# fab_scope.net
KiCad netlist of a schematic drawn in EAGLE
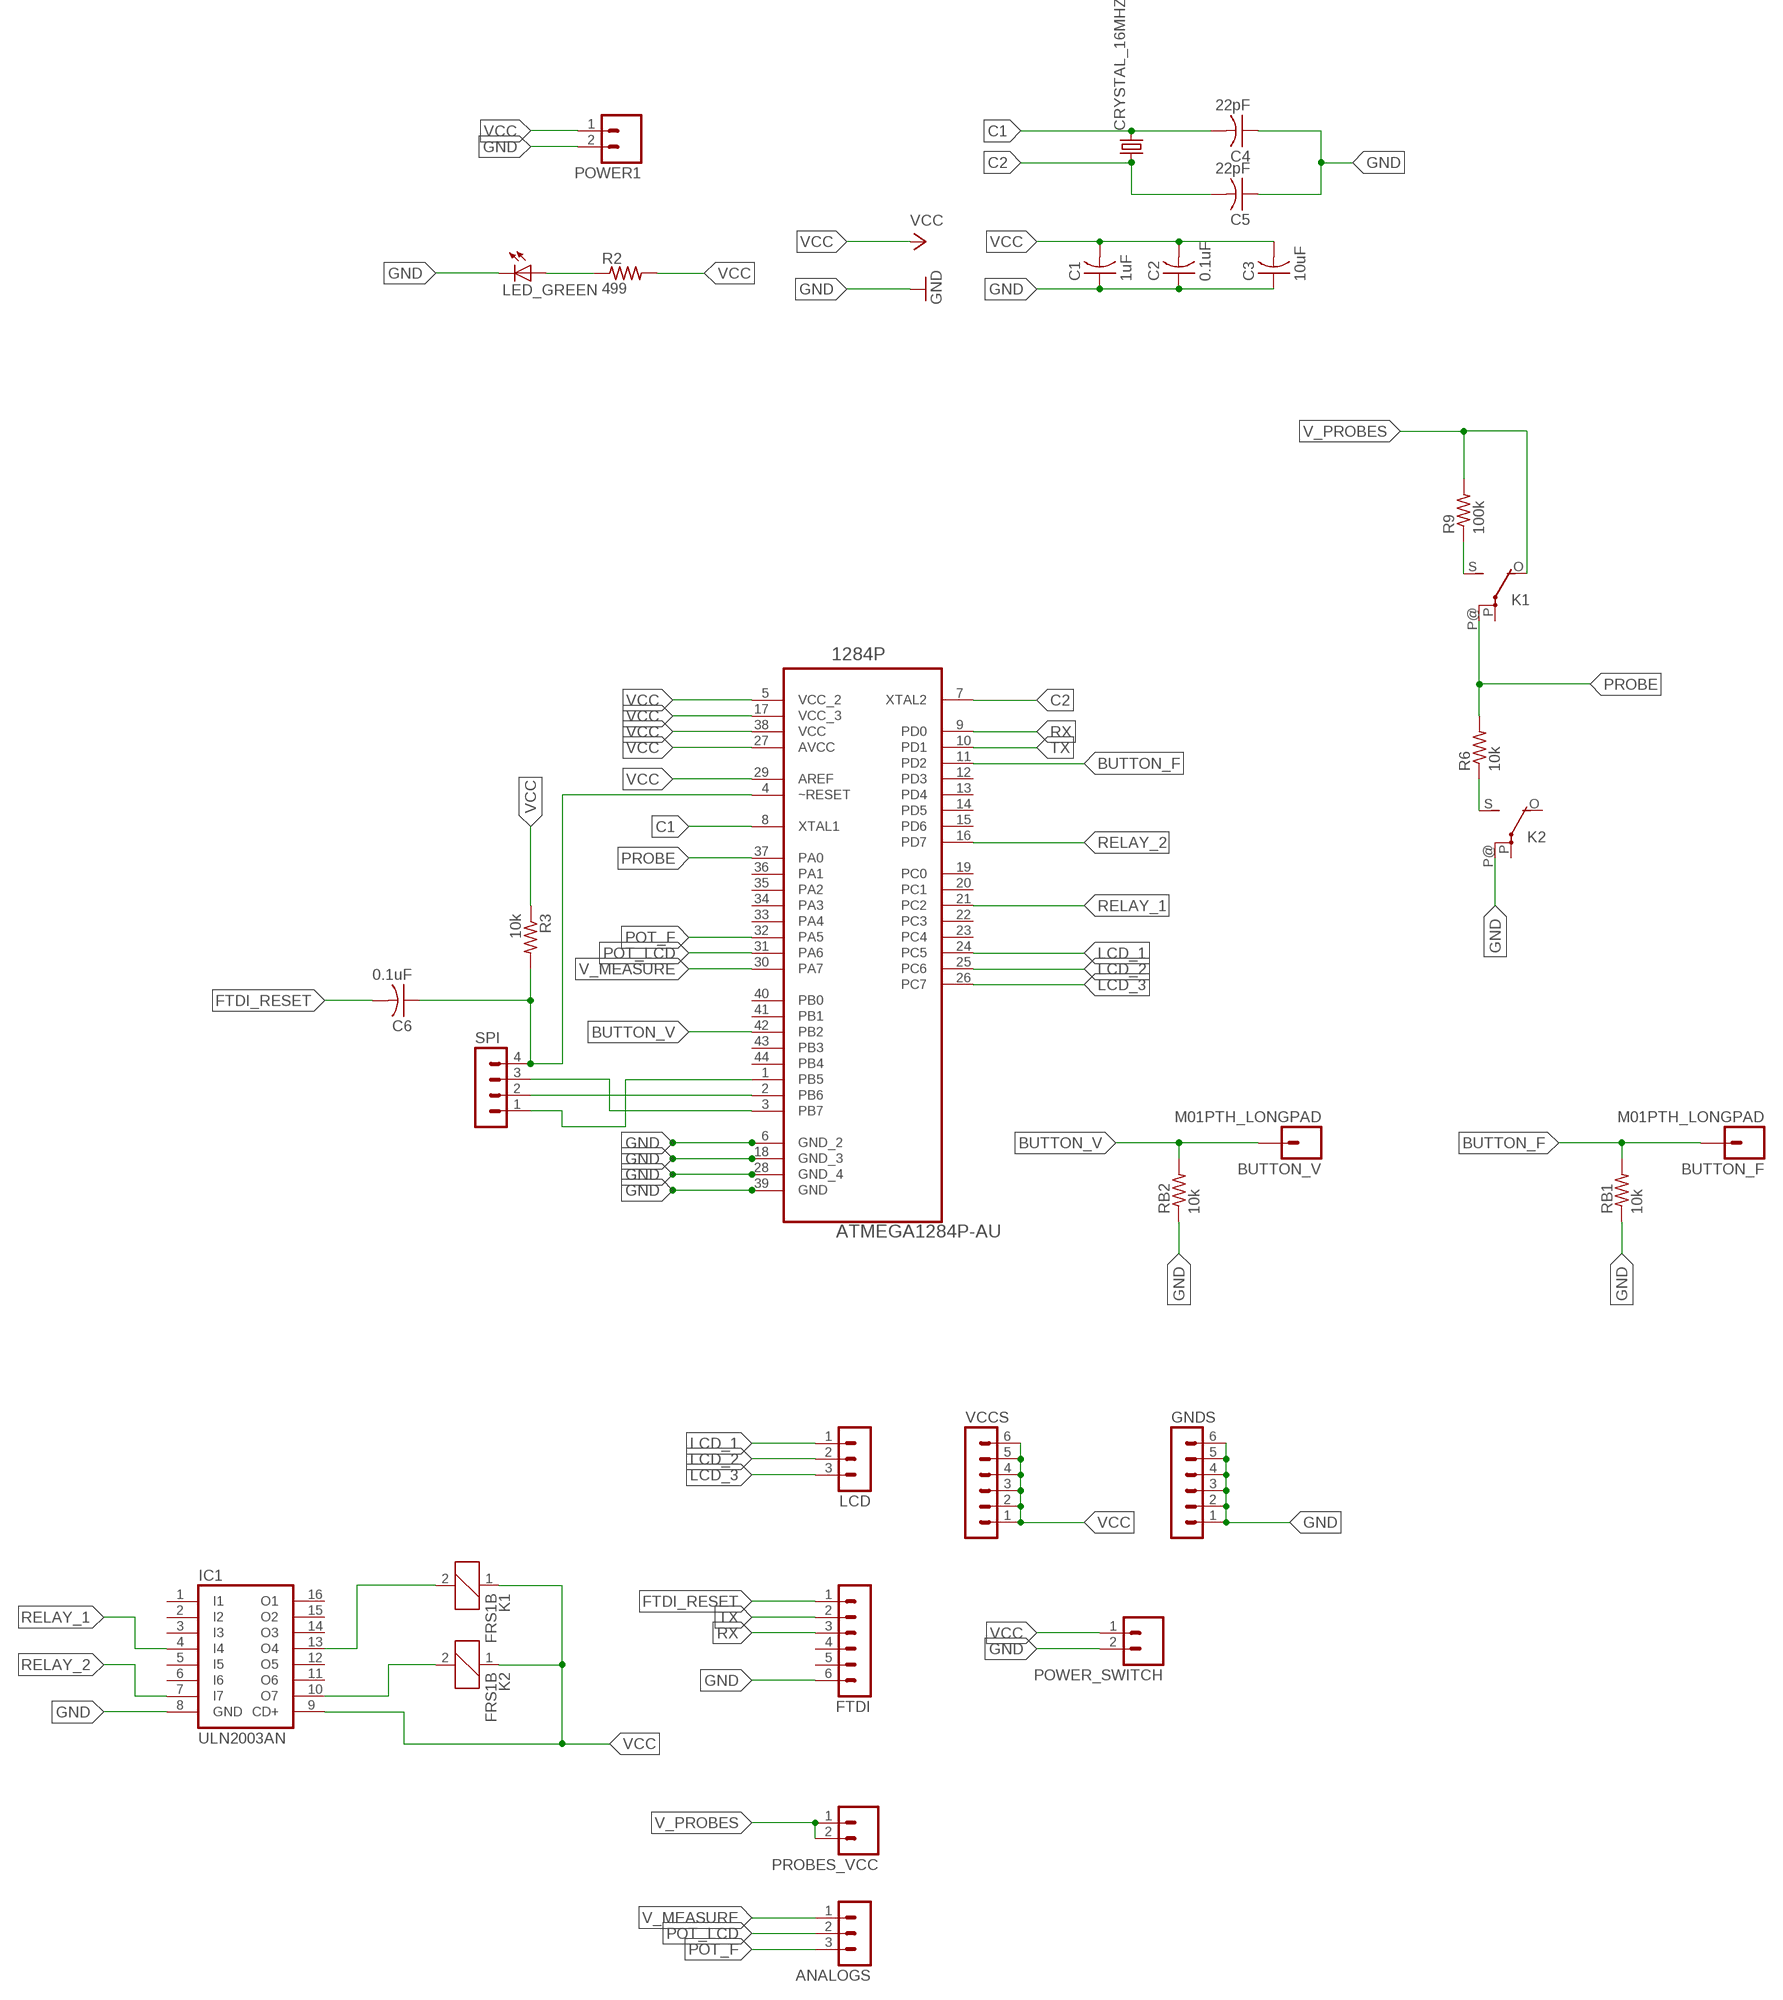
[diagram p0: schematic, sheet 1]

(export (version "E")
  (design (tool "Eeschema 10.0.6"))
  (components
    (comp (ref "1284P")
      (value "ATMEGA1284P-AU")
      (footprint "eagle-import:QFP80P1200X1200X120-44N")
      (libsource (lib "eagle-import") (part "ATMEGA1284P-AU"))
    )
    (comp (ref "ANALOGS")
      (value "MA03-1")
      (footprint "eagle-import:MA03-1")
      (libsource (lib "eagle-import") (part "MA03-1"))
    )
    (comp (ref "BUTTON_F")
      (value "M01PTH_LONGPAD")
      (footprint "eagle-import:1X01_LONGPAD")
      (libsource (lib "eagle-import") (part "M01PTH_LONGPAD"))
    )
    (comp (ref "BUTTON_V")
      (value "M01PTH_LONGPAD")
      (footprint "eagle-import:1X01_LONGPAD")
      (libsource (lib "eagle-import") (part "M01PTH_LONGPAD"))
    )
    (comp (ref "C1")
      (value "1uF")
      (footprint "eagle-import:C1206")
      (libsource (lib "eagle-import") (part "CAP-US1206"))
    )
    (comp (ref "C2")
      (value "0.1uF")
      (footprint "eagle-import:C1206")
      (libsource (lib "eagle-import") (part "CAP-US1206"))
    )
    (comp (ref "C3")
      (value "10uF")
      (footprint "eagle-import:C1206")
      (libsource (lib "eagle-import") (part "CAP-US1206"))
    )
    (comp (ref "C4")
      (value "22pF")
      (footprint "eagle-import:C1206")
      (libsource (lib "eagle-import") (part "CAP-US1206"))
    )
    (comp (ref "C5")
      (value "22pF")
      (footprint "eagle-import:C1206")
      (libsource (lib "eagle-import") (part "CAP-US1206"))
    )
    (comp (ref "C6")
      (value "0.1uF")
      (footprint "eagle-import:C1206")
      (libsource (lib "eagle-import") (part "CAP-US1206"))
    )
    (comp (ref "CRYSTAL_16MHZ")
      (value "CRYSTALHC49UP")
      (footprint "eagle-import:HC49UP")
      (libsource (lib "eagle-import") (part "CRYSTALHC49UP"))
    )
    (comp (ref "FTDI")
      (value "MA06-1")
      (footprint "eagle-import:MA06-1")
      (libsource (lib "eagle-import") (part "MA06-1"))
    )
    (comp (ref "GNDS")
      (value "MA06-1")
      (footprint "eagle-import:MA06-1")
      (libsource (lib "eagle-import") (part "MA06-1"))
    )
    (comp (ref "IC1")
      (value "ULN2003AN")
      (footprint "eagle-import:DIL16")
      (libsource (lib "eagle-import") (part "ULN2003AN"))
    )
    (comp (ref "K1")
      (value "FRS1B")
      (footprint "eagle-import:FRS1B")
      (libsource (lib "eagle-import") (part "FRS1B"))
    )
    (comp (ref "K2")
      (value "FRS1B")
      (footprint "eagle-import:FRS1B")
      (libsource (lib "eagle-import") (part "FRS1B"))
    )
    (comp (ref "LCD")
      (value "MA03-1")
      (footprint "eagle-import:MA03-1")
      (libsource (lib "eagle-import") (part "MA03-1"))
    )
    (comp (ref "LED_GREEN")
      (value "LED1206")
      (footprint "eagle-import:1206")
      (libsource (lib "eagle-import") (part "LED1206"))
    )
    (comp (ref "POWER1")
      (value "M02")
      (footprint "eagle-import:02P")
      (libsource (lib "eagle-import") (part "M02"))
    )
    (comp (ref "POWER_SWITCH")
      (value "M02")
      (footprint "eagle-import:02P")
      (libsource (lib "eagle-import") (part "M02"))
    )
    (comp (ref "PROBES_VCC")
      (value "M02")
      (footprint "eagle-import:02P")
      (libsource (lib "eagle-import") (part "M02"))
    )
    (comp (ref "R2")
      (value "499")
      (footprint "eagle-import:R1206")
      (libsource (lib "eagle-import") (part "RES-US1206"))
    )
    (comp (ref "R3")
      (value "10k")
      (footprint "eagle-import:R1206")
      (libsource (lib "eagle-import") (part "RES-US1206"))
    )
    (comp (ref "R6")
      (value "10k")
      (footprint "eagle-import:R1206")
      (libsource (lib "eagle-import") (part "RES-US1206"))
    )
    (comp (ref "R9")
      (value "100k")
      (footprint "eagle-import:R1206")
      (libsource (lib "eagle-import") (part "RES-US1206"))
    )
    (comp (ref "RB1")
      (value "10k")
      (footprint "eagle-import:R1206")
      (libsource (lib "eagle-import") (part "RES-US1206"))
    )
    (comp (ref "RB2")
      (value "10k")
      (footprint "eagle-import:R1206")
      (libsource (lib "eagle-import") (part "RES-US1206"))
    )
    (comp (ref "SPI")
      (value "MA04-1")
      (footprint "eagle-import:MA04-1")
      (libsource (lib "eagle-import") (part "MA04-1"))
    )
    (comp (ref "VCCS")
      (value "MA06-1")
      (footprint "eagle-import:MA06-1")
      (libsource (lib "eagle-import") (part "MA06-1"))
    )
  )
  (nets
    (net (code "1") (name "BUTTON_F") (class "Default")
      (node (ref "1284P") (pin "11") (pinfunction "PD2_11") (pintype "bidirectional"))
      (node (ref "BUTTON_F") (pin "1") (pinfunction "1_1") (pintype "passive"))
      (node (ref "RB1") (pin "2") (pinfunction "2_2") (pintype "passive"))
    )
    (net (code "2") (name "BUTTON_V") (class "Default")
      (node (ref "1284P") (pin "42") (pinfunction "PB2_42") (pintype "bidirectional"))
      (node (ref "BUTTON_V") (pin "1") (pinfunction "1_1") (pintype "passive"))
      (node (ref "RB2") (pin "2") (pinfunction "2_2") (pintype "passive"))
    )
    (net (code "3") (name "C1") (class "Default")
      (node (ref "1284P") (pin "8") (pinfunction "XTAL1_8") (pintype "input"))
      (node (ref "C4") (pin "2") (pinfunction "2_2") (pintype "passive"))
      (node (ref "CRYSTAL_16MHZ") (pin "2") (pinfunction "2_2") (pintype "passive"))
    )
    (net (code "4") (name "C2") (class "Default")
      (node (ref "1284P") (pin "7") (pinfunction "XTAL2_7") (pintype "output"))
      (node (ref "C5") (pin "2") (pinfunction "2_2") (pintype "passive"))
      (node (ref "CRYSTAL_16MHZ") (pin "1") (pinfunction "1_1") (pintype "passive"))
    )
    (net (code "5") (name "FTDI_RESET") (class "Default")
      (node (ref "C6") (pin "2") (pinfunction "2_2") (pintype "passive"))
      (node (ref "FTDI") (pin "1") (pinfunction "1_1") (pintype "passive"))
    )
    (net (code "6") (name "GND") (class "Default")
      (node (ref "1284P") (pin "6") (pinfunction "GND_2_6") (pintype "passive"))
      (node (ref "C1") (pin "1") (pinfunction "1_1") (pintype "passive"))
      (node (ref "C2") (pin "1") (pinfunction "1_1") (pintype "passive"))
      (node (ref "C3") (pin "1") (pinfunction "1_1") (pintype "passive"))
      (node (ref "C4") (pin "1") (pinfunction "1_1") (pintype "passive"))
      (node (ref "C5") (pin "1") (pinfunction "1_1") (pintype "passive"))
      (node (ref "FTDI") (pin "6") (pinfunction "6_6") (pintype "passive"))
      (node (ref "GNDS") (pin "1") (pinfunction "1_1") (pintype "passive"))
      (node (ref "GNDS") (pin "2") (pinfunction "2_2") (pintype "passive"))
      (node (ref "GNDS") (pin "3") (pinfunction "3_3") (pintype "passive"))
      (node (ref "GNDS") (pin "4") (pinfunction "4_4") (pintype "passive"))
      (node (ref "GNDS") (pin "5") (pinfunction "5_5") (pintype "passive"))
      (node (ref "GNDS") (pin "6") (pinfunction "6_6") (pintype "passive"))
      (node (ref "IC1") (pin "8") (pinfunction "GND_8") (pintype "power_in"))
      (node (ref "K2") (pin "P@") (pinfunction "P_P@") (pintype "passive"))
      (node (ref "LED_GREEN") (pin "2") (pinfunction "C_2") (pintype "passive"))
      (node (ref "POWER1") (pin "2") (pinfunction "2_2") (pintype "passive"))
      (node (ref "POWER_SWITCH") (pin "2") (pinfunction "2_2") (pintype "passive"))
      (node (ref "RB1") (pin "1") (pinfunction "1_1") (pintype "passive"))
      (node (ref "RB2") (pin "1") (pinfunction "1_1") (pintype "passive"))
    )
    (net (code "7") (name "LCD_1") (class "Default")
      (node (ref "1284P") (pin "24") (pinfunction "PC5_24") (pintype "bidirectional"))
      (node (ref "LCD") (pin "1") (pinfunction "1_1") (pintype "passive"))
    )
    (net (code "8") (name "LCD_2") (class "Default")
      (node (ref "1284P") (pin "25") (pinfunction "PC6_25") (pintype "bidirectional"))
      (node (ref "LCD") (pin "2") (pinfunction "2_2") (pintype "passive"))
    )
    (net (code "9") (name "LCD_3") (class "Default")
      (node (ref "1284P") (pin "26") (pinfunction "PC7_26") (pintype "bidirectional"))
      (node (ref "LCD") (pin "3") (pinfunction "3_3") (pintype "passive"))
    )
    (net (code "10") (name "Net-(1284P-PB5)") (class "Default")
      (node (ref "1284P") (pin "1") (pinfunction "PB5_1") (pintype "bidirectional"))
      (node (ref "SPI") (pin "1") (pinfunction "1_1") (pintype "passive"))
    )
    (net (code "11") (name "Net-(1284P-PB6)") (class "Default")
      (node (ref "1284P") (pin "2") (pinfunction "PB6_2") (pintype "bidirectional"))
      (node (ref "SPI") (pin "2") (pinfunction "2_2") (pintype "passive"))
    )
    (net (code "12") (name "Net-(1284P-PB7)") (class "Default")
      (node (ref "1284P") (pin "3") (pinfunction "PB7_3") (pintype "bidirectional"))
      (node (ref "SPI") (pin "3") (pinfunction "3_3") (pintype "passive"))
    )
    (net (code "13") (name "Net-(1284P-~{RESET})") (class "Default")
      (node (ref "1284P") (pin "4") (pinfunction "~{RESET}_4") (pintype "input"))
      (node (ref "C6") (pin "1") (pinfunction "1_1") (pintype "passive"))
      (node (ref "R3") (pin "2") (pinfunction "2_2") (pintype "passive"))
      (node (ref "SPI") (pin "4") (pinfunction "4_4") (pintype "passive"))
    )
    (net (code "14") (name "Net-(IC1-O4)") (class "Default")
      (node (ref "IC1") (pin "13") (pinfunction "O4_13") (pintype "open_collector"))
      (node (ref "K1") (pin "2") (pinfunction "2_2") (pintype "passive"))
    )
    (net (code "15") (name "Net-(IC1-O7)") (class "Default")
      (node (ref "IC1") (pin "10") (pinfunction "O7_10") (pintype "open_collector"))
      (node (ref "K2") (pin "2") (pinfunction "2_2") (pintype "passive"))
    )
    (net (code "16") (name "Net-(K1-PadS)") (class "Default")
      (node (ref "K1") (pin "S") (pinfunction "S_S") (pintype "passive"))
      (node (ref "R9") (pin "1") (pinfunction "1_1") (pintype "passive"))
    )
    (net (code "17") (name "Net-(K2-PadS)") (class "Default")
      (node (ref "K2") (pin "S") (pinfunction "S_S") (pintype "passive"))
      (node (ref "R6") (pin "1") (pinfunction "1_1") (pintype "passive"))
    )
    (net (code "18") (name "Net-(LED_GREEN-A)") (class "Default")
      (node (ref "LED_GREEN") (pin "1") (pinfunction "A_1") (pintype "passive"))
      (node (ref "R2") (pin "1") (pinfunction "1_1") (pintype "passive"))
    )
    (net (code "19") (name "POT_F") (class "Default")
      (node (ref "1284P") (pin "32") (pinfunction "PA5_32") (pintype "bidirectional"))
      (node (ref "ANALOGS") (pin "3") (pinfunction "3_3") (pintype "passive"))
    )
    (net (code "20") (name "POT_LCD") (class "Default")
      (node (ref "1284P") (pin "31") (pinfunction "PA6_31") (pintype "bidirectional"))
      (node (ref "ANALOGS") (pin "2") (pinfunction "2_2") (pintype "passive"))
    )
    (net (code "21") (name "PROBE") (class "Default")
      (node (ref "1284P") (pin "37") (pinfunction "PA0_37") (pintype "bidirectional"))
      (node (ref "K1") (pin "P@") (pinfunction "P_P@") (pintype "passive"))
      (node (ref "R6") (pin "2") (pinfunction "2_2") (pintype "passive"))
    )
    (net (code "22") (name "RELAY_1") (class "Default")
      (node (ref "1284P") (pin "21") (pinfunction "PC2_21") (pintype "bidirectional"))
      (node (ref "IC1") (pin "4") (pinfunction "I4_4") (pintype "input"))
    )
    (net (code "23") (name "RELAY_2") (class "Default")
      (node (ref "1284P") (pin "16") (pinfunction "PD7_16") (pintype "bidirectional"))
      (node (ref "IC1") (pin "7") (pinfunction "I7_7") (pintype "input"))
    )
    (net (code "24") (name "RX") (class "Default")
      (node (ref "1284P") (pin "9") (pinfunction "PD0_9") (pintype "bidirectional"))
      (node (ref "FTDI") (pin "3") (pinfunction "3_3") (pintype "passive"))
    )
    (net (code "25") (name "TX") (class "Default")
      (node (ref "1284P") (pin "10") (pinfunction "PD1_10") (pintype "bidirectional"))
      (node (ref "FTDI") (pin "2") (pinfunction "2_2") (pintype "passive"))
    )
    (net (code "26") (name "VCC") (class "Default")
      (node (ref "1284P") (pin "17") (pinfunction "VCC_3_17") (pintype "power_in"))
      (node (ref "1284P") (pin "27") (pinfunction "AVCC_27") (pintype "power_in"))
      (node (ref "1284P") (pin "29") (pinfunction "AREF_29") (pintype "input"))
      (node (ref "1284P") (pin "5") (pinfunction "VCC_2_5") (pintype "power_in"))
      (node (ref "C1") (pin "2") (pinfunction "2_2") (pintype "passive"))
      (node (ref "C2") (pin "2") (pinfunction "2_2") (pintype "passive"))
      (node (ref "C3") (pin "2") (pinfunction "2_2") (pintype "passive"))
      (node (ref "IC1") (pin "9") (pinfunction "CD+_9") (pintype "passive"))
      (node (ref "K1") (pin "1") (pinfunction "1_1") (pintype "passive"))
      (node (ref "K2") (pin "1") (pinfunction "1_1") (pintype "passive"))
      (node (ref "POWER1") (pin "1") (pinfunction "1_1") (pintype "passive"))
      (node (ref "POWER_SWITCH") (pin "1") (pinfunction "1_1") (pintype "passive"))
      (node (ref "R2") (pin "2") (pinfunction "2_2") (pintype "passive"))
      (node (ref "R3") (pin "1") (pinfunction "1_1") (pintype "passive"))
      (node (ref "VCCS") (pin "1") (pinfunction "1_1") (pintype "passive"))
      (node (ref "VCCS") (pin "2") (pinfunction "2_2") (pintype "passive"))
      (node (ref "VCCS") (pin "3") (pinfunction "3_3") (pintype "passive"))
      (node (ref "VCCS") (pin "4") (pinfunction "4_4") (pintype "passive"))
      (node (ref "VCCS") (pin "5") (pinfunction "5_5") (pintype "passive"))
      (node (ref "VCCS") (pin "6") (pinfunction "6_6") (pintype "passive"))
    )
    (net (code "27") (name "V_MEASURE") (class "Default")
      (node (ref "1284P") (pin "30") (pinfunction "PA7_30") (pintype "bidirectional"))
      (node (ref "ANALOGS") (pin "1") (pinfunction "1_1") (pintype "passive"))
    )
    (net (code "28") (name "V_PROBES") (class "Default")
      (node (ref "K1") (pin "O") (pinfunction "O_O") (pintype "passive"))
      (node (ref "PROBES_VCC") (pin "1") (pinfunction "1_1") (pintype "passive"))
      (node (ref "PROBES_VCC") (pin "2") (pinfunction "2_2") (pintype "passive"))
      (node (ref "R9") (pin "2") (pinfunction "2_2") (pintype "passive"))
    )
    (net (code "29") (name "unconnected-(1284P-GND-Pad39)") (class "Default")
      (node (ref "1284P") (pin "39") (pinfunction "GND_39") (pintype "passive"))
    )
    (net (code "30") (name "unconnected-(1284P-GND_3-Pad18)") (class "Default")
      (node (ref "1284P") (pin "18") (pinfunction "GND_3_18") (pintype "passive"))
    )
    (net (code "31") (name "unconnected-(1284P-GND_4-Pad28)") (class "Default")
      (node (ref "1284P") (pin "28") (pinfunction "GND_4_28") (pintype "passive"))
    )
    (net (code "32") (name "unconnected-(1284P-PA1-Pad36)") (class "Default")
      (node (ref "1284P") (pin "36") (pinfunction "PA1_36") (pintype "bidirectional"))
    )
    (net (code "33") (name "unconnected-(1284P-PA2-Pad35)") (class "Default")
      (node (ref "1284P") (pin "35") (pinfunction "PA2_35") (pintype "bidirectional"))
    )
    (net (code "34") (name "unconnected-(1284P-PA3-Pad34)") (class "Default")
      (node (ref "1284P") (pin "34") (pinfunction "PA3_34") (pintype "bidirectional"))
    )
    (net (code "35") (name "unconnected-(1284P-PA4-Pad33)") (class "Default")
      (node (ref "1284P") (pin "33") (pinfunction "PA4_33") (pintype "bidirectional"))
    )
    (net (code "36") (name "unconnected-(1284P-PB0-Pad40)") (class "Default")
      (node (ref "1284P") (pin "40") (pinfunction "PB0_40") (pintype "bidirectional"))
    )
    (net (code "37") (name "unconnected-(1284P-PB1-Pad41)") (class "Default")
      (node (ref "1284P") (pin "41") (pinfunction "PB1_41") (pintype "bidirectional"))
    )
    (net (code "38") (name "unconnected-(1284P-PB3-Pad43)") (class "Default")
      (node (ref "1284P") (pin "43") (pinfunction "PB3_43") (pintype "bidirectional"))
    )
    (net (code "39") (name "unconnected-(1284P-PB4-Pad44)") (class "Default")
      (node (ref "1284P") (pin "44") (pinfunction "PB4_44") (pintype "bidirectional"))
    )
    (net (code "40") (name "unconnected-(1284P-PC0-Pad19)") (class "Default")
      (node (ref "1284P") (pin "19") (pinfunction "PC0_19") (pintype "bidirectional"))
    )
    (net (code "41") (name "unconnected-(1284P-PC1-Pad20)") (class "Default")
      (node (ref "1284P") (pin "20") (pinfunction "PC1_20") (pintype "bidirectional"))
    )
    (net (code "42") (name "unconnected-(1284P-PC3-Pad22)") (class "Default")
      (node (ref "1284P") (pin "22") (pinfunction "PC3_22") (pintype "bidirectional"))
    )
    (net (code "43") (name "unconnected-(1284P-PC4-Pad23)") (class "Default")
      (node (ref "1284P") (pin "23") (pinfunction "PC4_23") (pintype "bidirectional"))
    )
    (net (code "44") (name "unconnected-(1284P-PD3-Pad12)") (class "Default")
      (node (ref "1284P") (pin "12") (pinfunction "PD3_12") (pintype "bidirectional"))
    )
    (net (code "45") (name "unconnected-(1284P-PD4-Pad13)") (class "Default")
      (node (ref "1284P") (pin "13") (pinfunction "PD4_13") (pintype "bidirectional"))
    )
    (net (code "46") (name "unconnected-(1284P-PD5-Pad14)") (class "Default")
      (node (ref "1284P") (pin "14") (pinfunction "PD5_14") (pintype "bidirectional"))
    )
    (net (code "47") (name "unconnected-(1284P-PD6-Pad15)") (class "Default")
      (node (ref "1284P") (pin "15") (pinfunction "PD6_15") (pintype "bidirectional"))
    )
    (net (code "48") (name "unconnected-(1284P-VCC-Pad38)") (class "Default")
      (node (ref "1284P") (pin "38") (pinfunction "VCC_38") (pintype "power_in"))
    )
    (net (code "49") (name "unconnected-(FTDI-Pad4)") (class "Default")
      (node (ref "FTDI") (pin "4") (pinfunction "4_4") (pintype "passive"))
    )
    (net (code "50") (name "unconnected-(FTDI-Pad5)") (class "Default")
      (node (ref "FTDI") (pin "5") (pinfunction "5_5") (pintype "passive"))
    )
    (net (code "51") (name "unconnected-(IC1-I1-Pad1)") (class "Default")
      (node (ref "IC1") (pin "1") (pinfunction "I1_1") (pintype "input"))
    )
    (net (code "52") (name "unconnected-(IC1-I2-Pad2)") (class "Default")
      (node (ref "IC1") (pin "2") (pinfunction "I2_2") (pintype "input"))
    )
    (net (code "53") (name "unconnected-(IC1-I3-Pad3)") (class "Default")
      (node (ref "IC1") (pin "3") (pinfunction "I3_3") (pintype "input"))
    )
    (net (code "54") (name "unconnected-(IC1-I5-Pad5)") (class "Default")
      (node (ref "IC1") (pin "5") (pinfunction "I5_5") (pintype "input"))
    )
    (net (code "55") (name "unconnected-(IC1-I6-Pad6)") (class "Default")
      (node (ref "IC1") (pin "6") (pinfunction "I6_6") (pintype "input"))
    )
    (net (code "56") (name "unconnected-(IC1-O1-Pad16)") (class "Default")
      (node (ref "IC1") (pin "16") (pinfunction "O1_16") (pintype "open_collector"))
    )
    (net (code "57") (name "unconnected-(IC1-O2-Pad15)") (class "Default")
      (node (ref "IC1") (pin "15") (pinfunction "O2_15") (pintype "open_collector"))
    )
    (net (code "58") (name "unconnected-(IC1-O3-Pad14)") (class "Default")
      (node (ref "IC1") (pin "14") (pinfunction "O3_14") (pintype "open_collector"))
    )
    (net (code "59") (name "unconnected-(IC1-O5-Pad12)") (class "Default")
      (node (ref "IC1") (pin "12") (pinfunction "O5_12") (pintype "open_collector"))
    )
    (net (code "60") (name "unconnected-(IC1-O6-Pad11)") (class "Default")
      (node (ref "IC1") (pin "11") (pinfunction "O6_11") (pintype "open_collector"))
    )
    (net (code "61") (name "unconnected-(K1-PadP)") (class "Default")
      (node (ref "K1") (pin "P") (pinfunction "P_P") (pintype "passive"))
    )
    (net (code "62") (name "unconnected-(K2-PadO)") (class "Default")
      (node (ref "K2") (pin "O") (pinfunction "O_O") (pintype "passive"))
    )
    (net (code "63") (name "unconnected-(K2-PadP)") (class "Default")
      (node (ref "K2") (pin "P") (pinfunction "P_P") (pintype "passive"))
    )
  )
)
